# Carrier_for-Addons-V01-002.net
KiCad netlist of a schematic drawn in EAGLE
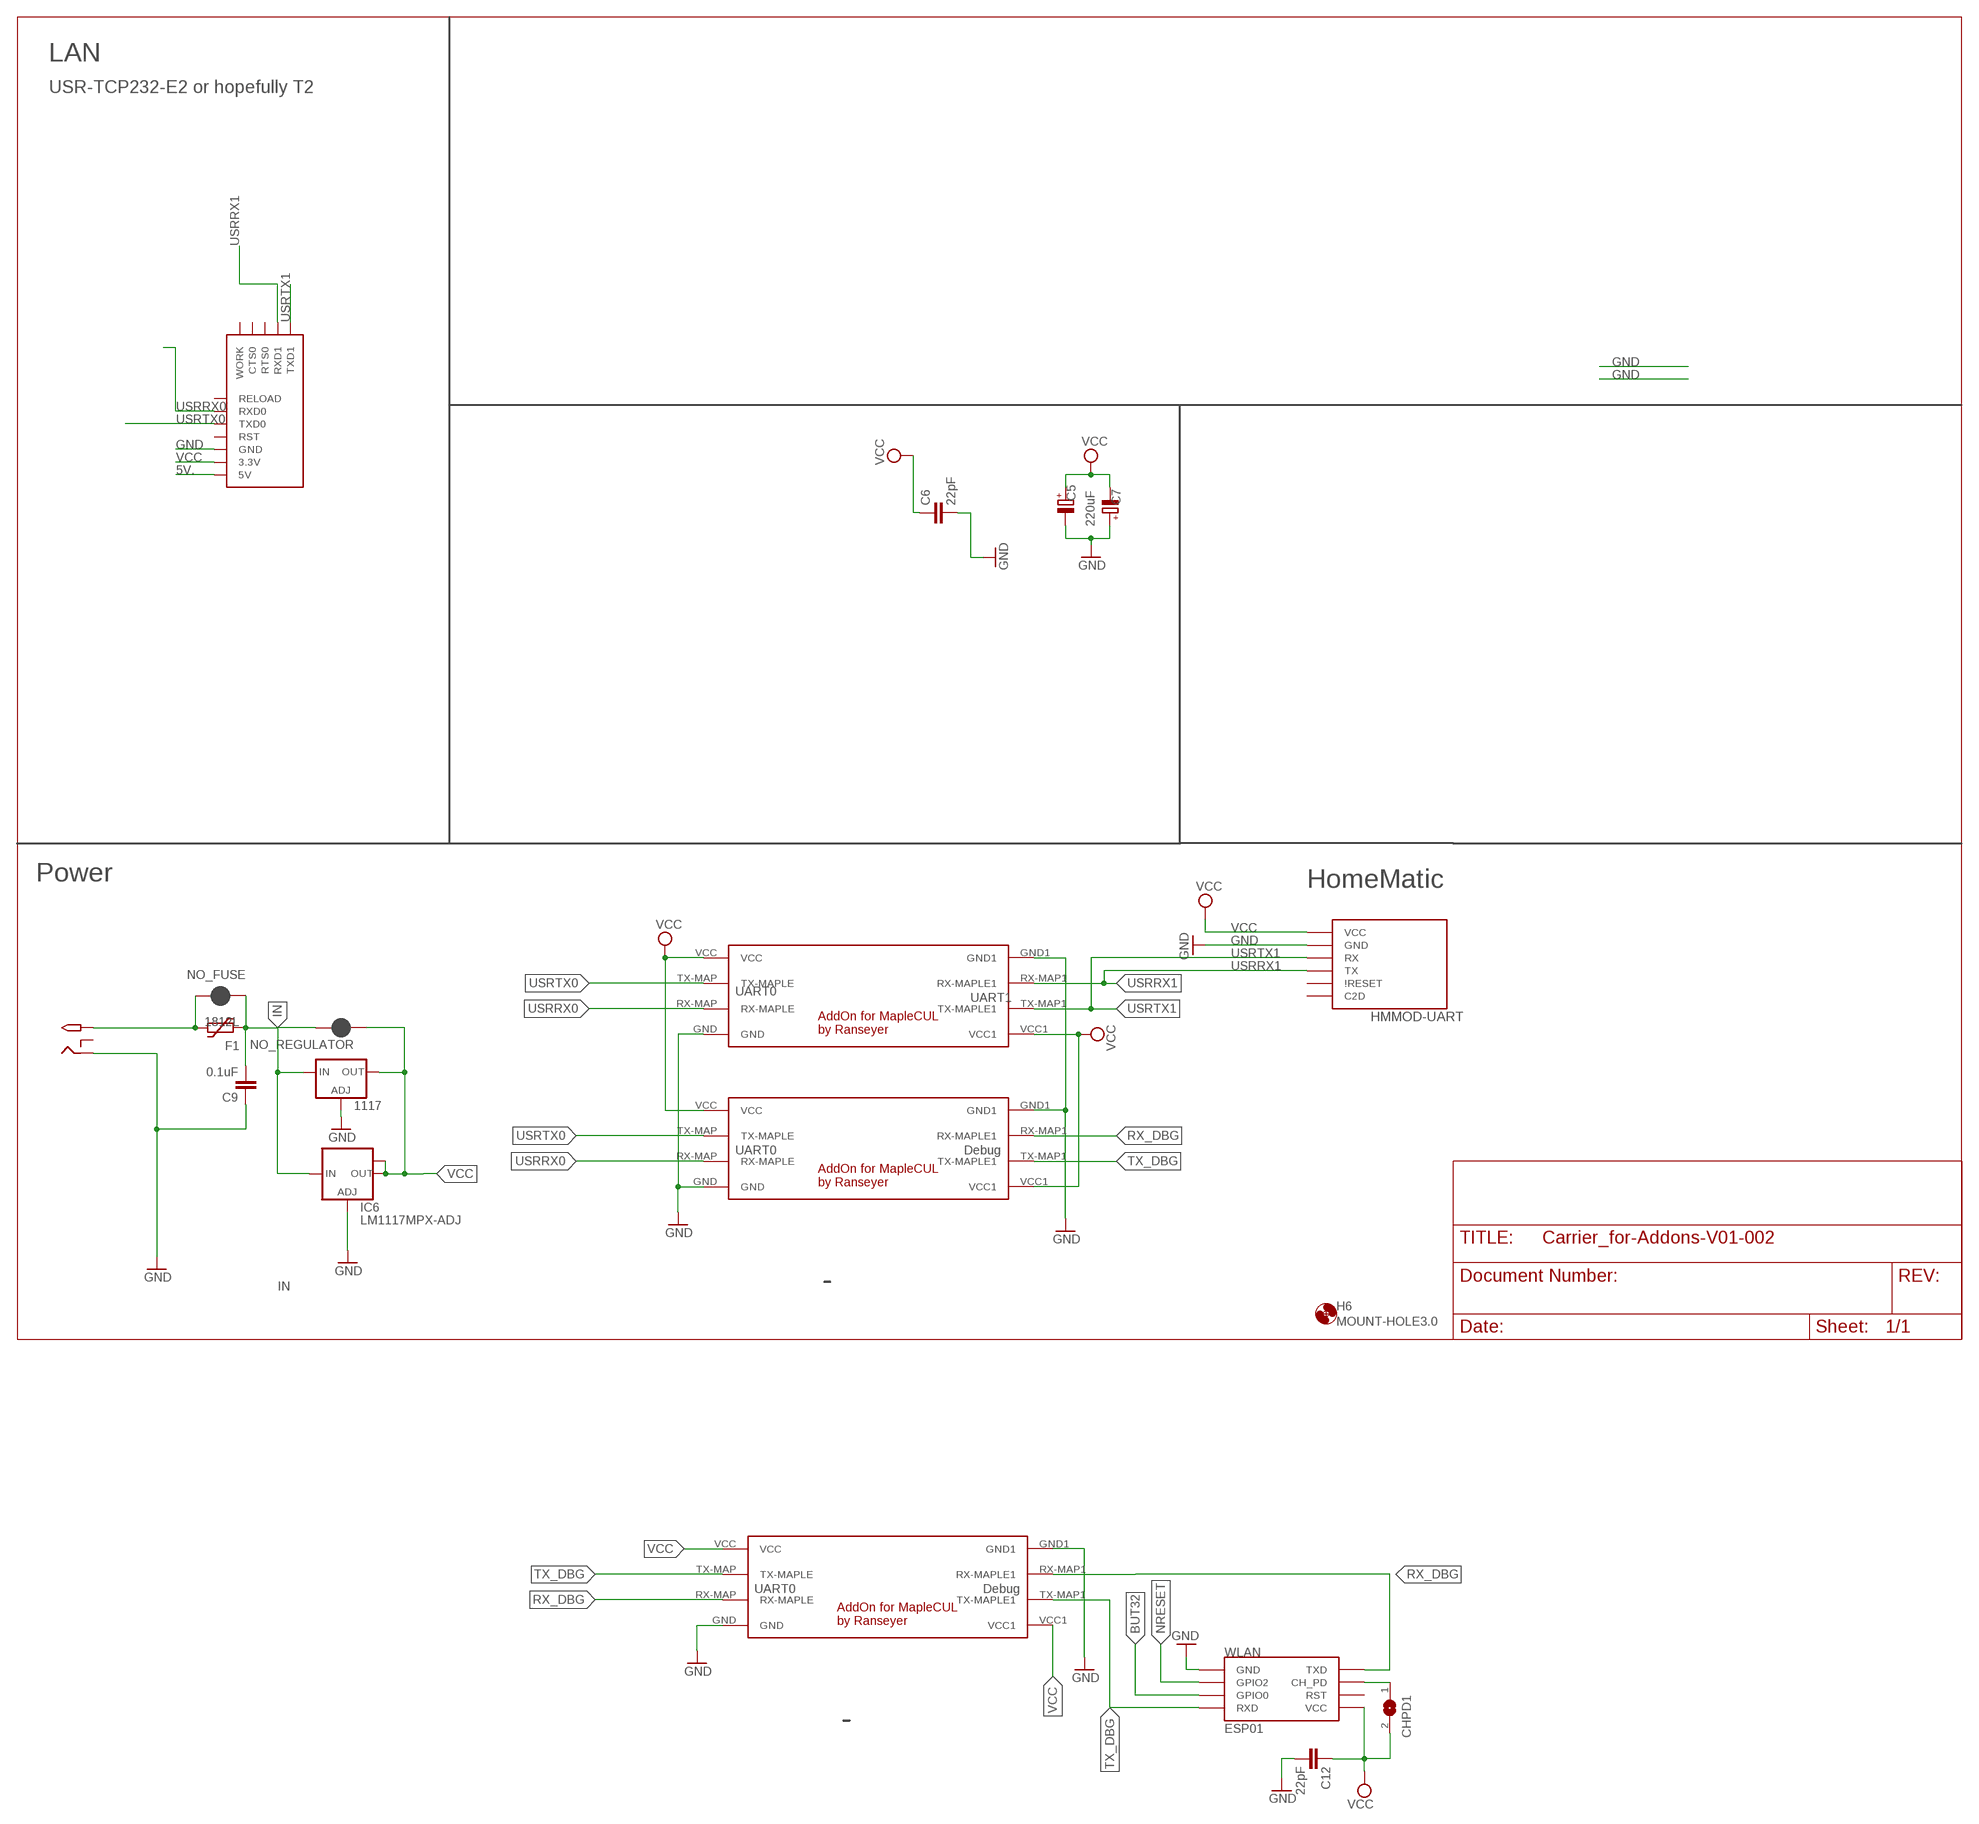
[diagram p0: schematic, sheet 1, part 1 of 2]
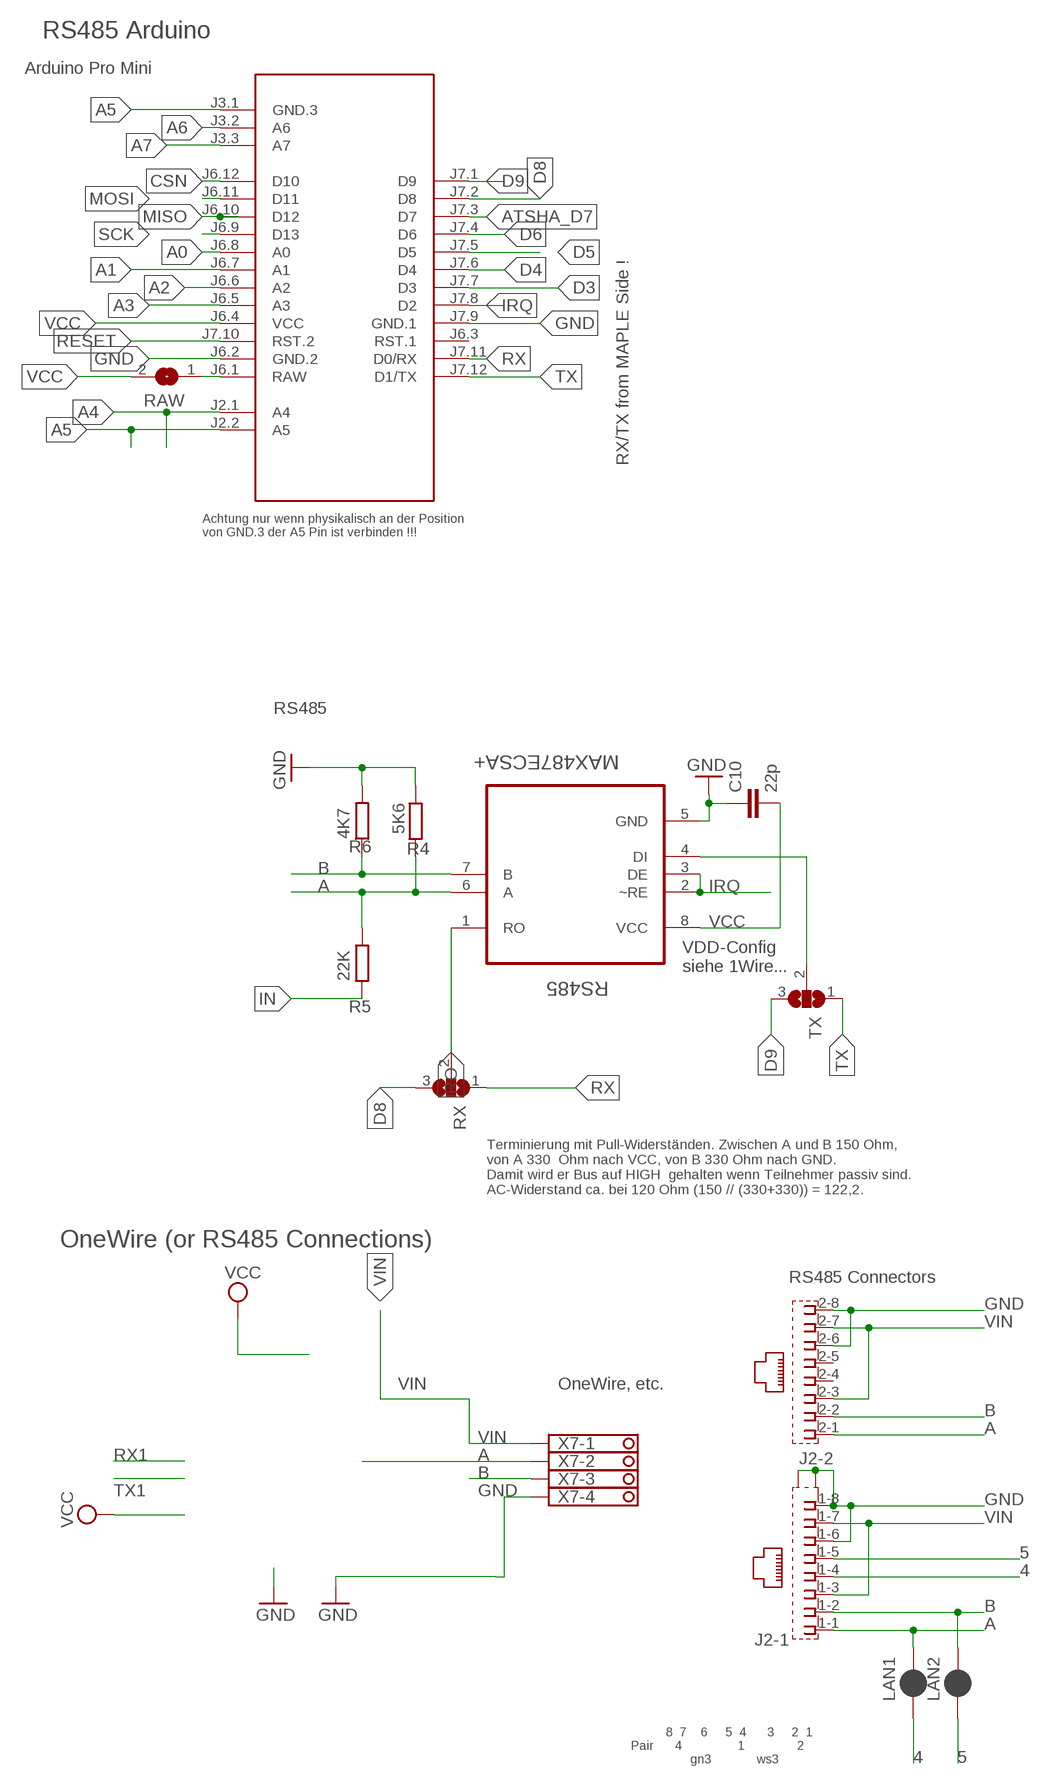
[diagram p1: schematic, sheet 1, part 2 of 2]

(export (version "E")
  (design (tool "Eeschema 10.0.6"))
  (components
    (comp (ref "1117")
      (value "LD117ADT50TR")
      (footprint "eagle-import:DPACK")
      (libsource (lib "eagle-import") (part "LD117A?DT50TR"))
    )
    (comp (ref "C5")
      (value "220uF")
      (footprint "eagle-import:E5-8,5")
      (libsource (lib "eagle-import") (part "CPOL-EUE5-8.5"))
    )
    (comp (ref "C6")
      (value "22pF")
      (footprint "eagle-import:C0805")
      (libsource (lib "eagle-import") (part "C-EUC0805"))
    )
    (comp (ref "C7")
      (value "CPOL-EUSMCE")
      (footprint "eagle-import:SMC_E")
      (libsource (lib "eagle-import") (part "rcl_334_CPOL-EUSMCE"))
    )
    (comp (ref "C9")
      (value "0.1uF")
      (footprint "eagle-import:C1206")
      (libsource (lib "eagle-import") (part "C-EUC1206"))
    )
    (comp (ref "C10")
      (value "22p")
      (footprint "eagle-import:C0805")
      (libsource (lib "eagle-import") (part "C-EUC0805"))
    )
    (comp (ref "C12")
      (value "22pF")
      (footprint "eagle-import:C0805")
      (libsource (lib "eagle-import") (part "C-EUC0805"))
    )
    (comp (ref "CHPD1")
      (value "SJ")
      (footprint "eagle-import:SJ")
      (libsource (lib "eagle-import") (part "jumper_252_SJ"))
    )
    (comp (ref "F1")
      (value "1812L")
      (footprint "eagle-import:1812L")
      (libsource (lib "eagle-import") (part "1812L"))
    )
    (comp (ref "H6")
      (value "MOUNT-HOLE3.0")
      (footprint "eagle-import:3,0")
      (libsource (lib "eagle-import") (part "MOUNT-HOLE3.0"))
    )
    (comp (ref "HMMOD-UART")
      (value "HM-MOD-UARTDIL")
      (footprint "eagle-import:HM-MOD-UART-DIL")
      (libsource (lib "eagle-import") (part "HM-MOD-UARTDIL"))
    )
    (comp (ref "IC6")
      (value "LM1117MPX-ADJ")
      (footprint "eagle-import:SOT223")
      (libsource (lib "eagle-import") (part "LM1117MPX-ADJ"))
    )
    (comp (ref "J2")
      (value "RJ45_2X_S")
      (footprint "eagle-import:RJ45_2X_S")
      (libsource (lib "eagle-import") (part "RJ45_2X_S"))
    )
    (comp (ref "LAN1")
      (value "JUMPER-SMT_2_NC_PASTE_SILK")
      (footprint "eagle-import:SMT-JUMPER_2_NC_PASTE_SILK")
      (libsource (lib "eagle-import") (part "JUMPER-SMT_2_NC_PASTE_SILK"))
    )
    (comp (ref "LAN2")
      (value "JUMPER-SMT_2_NC_PASTE_SILK")
      (footprint "eagle-import:SMT-JUMPER_2_NC_PASTE_SILK")
      (libsource (lib "eagle-import") (part "JUMPER-SMT_2_NC_PASTE_SILK"))
    )
    (comp (ref "M1")
      (value "ARDUINO-PRO-MINI-3.3V#NP")
      (footprint "eagle-import:ARDUINO-PRO-MINI#NP")
      (libsource (lib "eagle-import") (part "ARDUINO-PRO-MINI-#NP3.3V"))
    )
    (comp (ref "NO_FUSE")
      (value "JUMPER-SMT_2_NC_PASTE_NO-SILK")
      (footprint "eagle-import:SMT-JUMPER_2_NC_PASTE_NO-SILK")
      (libsource (lib "eagle-import") (part "SparkFun-Jumpers_528_JUMPER-SMT_2_NC_PASTE_NO-SILK"))
    )
    (comp (ref "NO_REGULATOR")
      (value "JUMPER-SMT_2_NC_PASTE_NO-SILK")
      (footprint "eagle-import:SMT-JUMPER_2_NC_PASTE_NO-SILK")
      (libsource (lib "eagle-import") (part "SparkFun-Jumpers_528_JUMPER-SMT_2_NC_PASTE_NO-SILK"))
    )
    (comp (ref "R4")
      (value "5K6")
      (footprint "eagle-import:R0805")
      (libsource (lib "eagle-import") (part "R-EU_R0805"))
    )
    (comp (ref "R5")
      (value "22K")
      (footprint "eagle-import:R0805")
      (libsource (lib "eagle-import") (part "R-EU_R0805"))
    )
    (comp (ref "R6")
      (value "4K7")
      (footprint "eagle-import:R0805")
      (libsource (lib "eagle-import") (part "R-EU_R0805"))
    )
    (comp (ref "RAW") (value "SJ") (footprint "eagle-import:SJ") (libsource (lib "eagle-import") (part "SJ")))
    (comp (ref "RS485")
      (value "MAX487ECSA+")
      (footprint "eagle-import:SOIC127P600X175-8N")
      (libsource (lib "eagle-import") (part "MAX487ECSA+"))
    )
    (comp (ref "RX")
      (value "SJ2W")
      (footprint "eagle-import:SJ_2")
      (libsource (lib "eagle-import") (part "SJ2W"))
    )
    (comp (ref "TX")
      (value "SJ2W")
      (footprint "eagle-import:SJ_2")
      (libsource (lib "eagle-import") (part "SJ2W"))
    )
    (comp (ref "U$1")
      (value "MAPLE-CUL-ADDON-V01")
      (footprint "eagle-import:MAPLE-CUL-V01")
      (libsource (lib "eagle-import") (part "MAPLE-CUL-ADDON-V01"))
    )
    (comp (ref "U$2")
      (value "2.1MMJACKTHM")
      (footprint "eagle-import:PJ-102A")
      (libsource (lib "eagle-import") (part "2.1MMJACKTHM"))
    )
    (comp (ref "U$3")
      (value "MAPLE-CUL-ADDON-V01")
      (footprint "eagle-import:MAPLE-CUL-V01")
      (libsource (lib "eagle-import") (part "MAPLE-CUL-ADDON-V01"))
    )
    (comp (ref "U$4")
      (value "MAPLE-CUL-ADDON-V01")
      (footprint "eagle-import:MAPLE-CUL-V01")
      (libsource (lib "eagle-import") (part "MAPLE-CUL-ADDON-V01"))
    )
    (comp (ref "U$5")
      (value "USR-TCP232-E2")
      (footprint "eagle-import:USR-TCP232-E2")
      (libsource (lib "eagle-import") (part "USR-TCP232-E2"))
    )
    (comp (ref "WLAN")
      (value "ESP01")
      (footprint "eagle-import:ESP01")
      (libsource (lib "eagle-import") (part "ESP01"))
    )
    (comp (ref "X7")
      (value "1751264")
      (footprint "eagle-import:1751264")
      (libsource (lib "eagle-import") (part "1751264"))
    )
  )
  (nets
    (net (code "1") (name "/4") (class "Default")
      (node (ref "J2") (pin "1-4") (pinfunction "4_1-4") (pintype "passive"))
      (node (ref "LAN1") (pin "1") (pinfunction "1_1") (pintype "passive"))
    )
    (net (code "2") (name "/5") (class "Default")
      (node (ref "J2") (pin "1-5") (pinfunction "5_1-5") (pintype "passive"))
      (node (ref "LAN2") (pin "1") (pinfunction "1_1") (pintype "passive"))
    )
    (net (code "3") (name "/5V.") (class "Default")
      (node (ref "U$5") (pin "5V") (pinfunction "5V_5V") (pintype "bidirectional"))
    )
    (net (code "4") (name "/A") (class "Default")
      (node (ref "J2") (pin "1-1") (pinfunction "1_1-1") (pintype "passive"))
      (node (ref "J2") (pin "2-1") (pinfunction "1_2-1") (pintype "passive"))
      (node (ref "LAN1") (pin "2") (pinfunction "2_2") (pintype "passive"))
      (node (ref "R4") (pin "2") (pinfunction "2_2") (pintype "passive"))
      (node (ref "R5") (pin "2") (pinfunction "2_2") (pintype "passive"))
      (node (ref "RS485") (pin "6") (pinfunction "A_6") (pintype "bidirectional"))
      (node (ref "X7") (pin "2") (pinfunction "K_2") (pintype "passive"))
    )
    (net (code "5") (name "/B") (class "Default")
      (node (ref "J2") (pin "1-2") (pinfunction "2_1-2") (pintype "passive"))
      (node (ref "J2") (pin "2-2") (pinfunction "2_2-2") (pintype "passive"))
      (node (ref "LAN2") (pin "2") (pinfunction "2_2") (pintype "passive"))
      (node (ref "R6") (pin "1") (pinfunction "1_1") (pintype "passive"))
      (node (ref "RS485") (pin "7") (pinfunction "B_7") (pintype "bidirectional"))
      (node (ref "X7") (pin "3") (pinfunction "K_3") (pintype "passive"))
    )
    (net (code "8") (name "A0") (class "Default")
      (node (ref "M1") (pin "J6.8") (pinfunction "A0_J6.8") (pintype "bidirectional"))
    )
    (net (code "9") (name "A1") (class "Default")
      (node (ref "M1") (pin "J6.7") (pinfunction "A1_J6.7") (pintype "bidirectional"))
    )
    (net (code "10") (name "A2") (class "Default")
      (node (ref "M1") (pin "J6.6") (pinfunction "A2_J6.6") (pintype "bidirectional"))
    )
    (net (code "11") (name "A3") (class "Default")
      (node (ref "M1") (pin "J6.5") (pinfunction "A3_J6.5") (pintype "bidirectional"))
    )
    (net (code "12") (name "A4") (class "Default")
      (node (ref "M1") (pin "J2.1") (pinfunction "A4_J2.1") (pintype "bidirectional"))
    )
    (net (code "13") (name "A5") (class "Default")
      (node (ref "M1") (pin "J2.2") (pinfunction "A5_J2.2") (pintype "bidirectional"))
      (node (ref "M1") (pin "J3.1") (pinfunction "GND.3_J3.1") (pintype "bidirectional"))
    )
    (net (code "14") (name "A6") (class "Default")
      (node (ref "M1") (pin "J3.2") (pinfunction "A6_J3.2") (pintype "bidirectional"))
    )
    (net (code "15") (name "A7") (class "Default")
      (node (ref "M1") (pin "J3.3") (pinfunction "A7_J3.3") (pintype "bidirectional"))
    )
    (net (code "16") (name "ATSHA_D7") (class "Default")
      (node (ref "M1") (pin "J7.3") (pinfunction "D7_J7.3") (pintype "bidirectional"))
    )
    (net (code "17") (name "BUT32") (class "Default")
      (node (ref "WLAN") (pin "GPIO0") (pinfunction "GPIO0_GPIO0") (pintype "bidirectional"))
    )
    (net (code "18") (name "CSN") (class "Default")
      (node (ref "M1") (pin "J6.12") (pinfunction "D10_J6.12") (pintype "bidirectional"))
    )
    (net (code "19") (name "D3") (class "Default")
      (node (ref "M1") (pin "J7.7") (pinfunction "D3_J7.7") (pintype "bidirectional"))
    )
    (net (code "20") (name "D4") (class "Default")
      (node (ref "M1") (pin "J7.6") (pinfunction "D4_J7.6") (pintype "bidirectional"))
    )
    (net (code "21") (name "D5") (class "Default")
      (node (ref "M1") (pin "J7.5") (pinfunction "D5_J7.5") (pintype "bidirectional"))
    )
    (net (code "22") (name "D6") (class "Default")
      (node (ref "M1") (pin "J7.4") (pinfunction "D6_J7.4") (pintype "bidirectional"))
    )
    (net (code "23") (name "D8") (class "Default")
      (node (ref "M1") (pin "J7.2") (pinfunction "D8_J7.2") (pintype "bidirectional"))
      (node (ref "RX") (pin "3") (pinfunction "3_3") (pintype "passive"))
    )
    (net (code "24") (name "D9") (class "Default")
      (node (ref "M1") (pin "J7.1") (pinfunction "D9_J7.1") (pintype "bidirectional"))
      (node (ref "TX") (pin "3") (pinfunction "3_3") (pintype "passive"))
    )
    (net (code "25") (name "GND") (class "Default")
      (node (ref "1117") (pin "1") (pinfunction "ADJ_1") (pintype "input"))
      (node (ref "C10") (pin "1") (pinfunction "1_1") (pintype "passive"))
      (node (ref "C12") (pin "2") (pinfunction "2_2") (pintype "passive"))
      (node (ref "C5") (pin "-") (pinfunction "-_-") (pintype "passive"))
      (node (ref "C6") (pin "2") (pinfunction "2_2") (pintype "passive"))
      (node (ref "C7") (pin "+") (pinfunction "+_+") (pintype "passive"))
      (node (ref "C9") (pin "1") (pinfunction "1_1") (pintype "passive"))
      (node (ref "HMMOD-UART") (pin "2") (pinfunction "GND_2") (pintype "power_in"))
      (node (ref "IC6") (pin "1") (pinfunction "ADJ_1") (pintype "input"))
      (node (ref "J2") (pin "1-6") (pinfunction "6_1-6") (pintype "passive"))
      (node (ref "J2") (pin "1-8") (pinfunction "8_1-8") (pintype "passive"))
      (node (ref "J2") (pin "2-6") (pinfunction "6_2-6") (pintype "passive"))
      (node (ref "J2") (pin "2-8") (pinfunction "8_2-8") (pintype "passive"))
      (node (ref "J2") (pin "G1") (pinfunction "S2_G1") (pintype "passive"))
      (node (ref "J2") (pin "G3") (pinfunction "S1_G3") (pintype "passive"))
      (node (ref "M1") (pin "J6.2") (pinfunction "GND.2_J6.2") (pintype "power_in"))
      (node (ref "M1") (pin "J7.9") (pinfunction "GND.1_J7.9") (pintype "power_in"))
      (node (ref "R4") (pin "1") (pinfunction "1_1") (pintype "passive"))
      (node (ref "R6") (pin "2") (pinfunction "2_2") (pintype "passive"))
      (node (ref "RS485") (pin "5") (pinfunction "GND_5") (pintype "passive"))
      (node (ref "U$1") (pin "GND") (pinfunction "GND_GND") (pintype "bidirectional"))
      (node (ref "U$1") (pin "GND1") (pinfunction "GND1_GND1") (pintype "bidirectional"))
      (node (ref "U$2") (pin "RING") (pinfunction "RING_RING") (pintype "bidirectional"))
      (node (ref "U$3") (pin "GND") (pinfunction "GND_GND") (pintype "bidirectional"))
      (node (ref "U$3") (pin "GND1") (pinfunction "GND1_GND1") (pintype "bidirectional"))
      (node (ref "U$4") (pin "GND") (pinfunction "GND_GND") (pintype "bidirectional"))
      (node (ref "U$4") (pin "GND1") (pinfunction "GND1_GND1") (pintype "bidirectional"))
      (node (ref "U$5") (pin "GND") (pinfunction "GND_GND") (pintype "bidirectional"))
      (node (ref "WLAN") (pin "GND") (pinfunction "GND_GND") (pintype "bidirectional"))
      (node (ref "X7") (pin "4") (pinfunction "K_4") (pintype "passive"))
    )
    (net (code "26") (name "IN") (class "Default")
      (node (ref "1117") (pin "3") (pinfunction "IN_3") (pintype "input"))
      (node (ref "C9") (pin "2") (pinfunction "2_2") (pintype "passive"))
      (node (ref "F1") (pin "P$1") (pinfunction "1_P$1") (pintype "passive"))
      (node (ref "IC6") (pin "3") (pinfunction "IN_3") (pintype "input"))
      (node (ref "NO_FUSE") (pin "1") (pinfunction "1_1") (pintype "passive"))
      (node (ref "NO_REGULATOR") (pin "2") (pinfunction "2_2") (pintype "passive"))
      (node (ref "R5") (pin "1") (pinfunction "1_1") (pintype "passive"))
    )
    (net (code "27") (name "IRQ") (class "Default")
      (node (ref "M1") (pin "J7.8") (pinfunction "D2_J7.8") (pintype "bidirectional"))
      (node (ref "RS485") (pin "2") (pinfunction "~{RE}_2") (pintype "input"))
      (node (ref "RS485") (pin "3") (pinfunction "DE_3") (pintype "input"))
    )
    (net (code "28") (name "MISO") (class "Default")
      (node (ref "M1") (pin "J6.10") (pinfunction "D12_J6.10") (pintype "bidirectional"))
    )
    (net (code "29") (name "MOSI") (class "Default")
      (node (ref "M1") (pin "J6.11") (pinfunction "D11_J6.11") (pintype "bidirectional"))
    )
    (net (code "30") (name "NRESET") (class "Default")
      (node (ref "WLAN") (pin "GPIO2") (pinfunction "GPIO2_GPIO2") (pintype "bidirectional"))
    )
    (net (code "31") (name "Net-(CHPD1-Pad1)") (class "Default")
      (node (ref "CHPD1") (pin "1") (pinfunction "1_1") (pintype "passive"))
      (node (ref "WLAN") (pin "CH_PD") (pinfunction "CH_PD_CH_PD") (pintype "bidirectional"))
    )
    (net (code "32") (name "Net-(M1-RAW)") (class "Default")
      (node (ref "M1") (pin "J6.1") (pinfunction "RAW_J6.1") (pintype "power_in"))
      (node (ref "RAW") (pin "1") (pinfunction "1_1") (pintype "passive"))
    )
    (net (code "33") (name "Net-(RS485-DI)") (class "Default")
      (node (ref "RS485") (pin "4") (pinfunction "DI_4") (pintype "input"))
      (node (ref "TX") (pin "2") (pinfunction "2_2") (pintype "passive"))
    )
    (net (code "34") (name "RESET") (class "Default")
      (node (ref "M1") (pin "J7.10") (pinfunction "RST.2_J7.10") (pintype "bidirectional"))
    )
    (net (code "35") (name "RO") (class "Default")
      (node (ref "RS485") (pin "1") (pinfunction "RO_1") (pintype "output"))
      (node (ref "RX") (pin "2") (pinfunction "2_2") (pintype "passive"))
    )
    (net (code "36") (name "RX") (class "Default")
      (node (ref "M1") (pin "J7.11") (pinfunction "D0/RX_J7.11") (pintype "bidirectional"))
      (node (ref "RX") (pin "1") (pinfunction "1_1") (pintype "passive"))
    )
    (net (code "37") (name "RX_DBG") (class "Default")
      (node (ref "U$1") (pin "RX-MAP") (pinfunction "RX-MAPLE_RX-MAP") (pintype "bidirectional"))
      (node (ref "U$1") (pin "RX-MAP1") (pinfunction "RX-MAPLE1_RX-MAP1") (pintype "bidirectional"))
      (node (ref "U$4") (pin "RX-MAP1") (pinfunction "RX-MAPLE1_RX-MAP1") (pintype "bidirectional"))
      (node (ref "WLAN") (pin "TX") (pinfunction "TXD_TX") (pintype "bidirectional"))
    )
    (net (code "38") (name "SCK") (class "Default")
      (node (ref "M1") (pin "J6.9") (pinfunction "D13_J6.9") (pintype "bidirectional"))
    )
    (net (code "39") (name "TX") (class "Default")
      (node (ref "M1") (pin "J7.12") (pinfunction "D1/TX_J7.12") (pintype "bidirectional"))
      (node (ref "TX") (pin "1") (pinfunction "1_1") (pintype "passive"))
    )
    (net (code "40") (name "TX_DBG") (class "Default")
      (node (ref "U$1") (pin "TX-MAP") (pinfunction "TX-MAPLE_TX-MAP") (pintype "bidirectional"))
      (node (ref "U$1") (pin "TX-MAP1") (pinfunction "TX-MAPLE1_TX-MAP1") (pintype "bidirectional"))
      (node (ref "U$4") (pin "TX-MAP1") (pinfunction "TX-MAPLE1_TX-MAP1") (pintype "bidirectional"))
      (node (ref "WLAN") (pin "RX") (pinfunction "RXD_RX") (pintype "bidirectional"))
    )
    (net (code "41") (name "USRRX0") (class "Default")
      (node (ref "U$3") (pin "RX-MAP") (pinfunction "RX-MAPLE_RX-MAP") (pintype "bidirectional"))
      (node (ref "U$4") (pin "RX-MAP") (pinfunction "RX-MAPLE_RX-MAP") (pintype "bidirectional"))
      (node (ref "U$5") (pin "RXD0") (pinfunction "RXD0_RXD0") (pintype "input"))
    )
    (net (code "42") (name "USRRX1") (class "Default")
      (node (ref "HMMOD-UART") (pin "5") (pinfunction "TX_5") (pintype "bidirectional"))
      (node (ref "U$3") (pin "RX-MAP1") (pinfunction "RX-MAPLE1_RX-MAP1") (pintype "bidirectional"))
      (node (ref "U$5") (pin "RXD1") (pinfunction "RXD1_RXD1") (pintype "input"))
    )
    (net (code "43") (name "USRTX0") (class "Default")
      (node (ref "U$3") (pin "TX-MAP") (pinfunction "TX-MAPLE_TX-MAP") (pintype "bidirectional"))
      (node (ref "U$4") (pin "TX-MAP") (pinfunction "TX-MAPLE_TX-MAP") (pintype "bidirectional"))
      (node (ref "U$5") (pin "TXD0") (pinfunction "TXD0_TXD0") (pintype "output"))
    )
    (net (code "44") (name "USRTX1") (class "Default")
      (node (ref "HMMOD-UART") (pin "6") (pinfunction "RX_6") (pintype "bidirectional"))
      (node (ref "U$3") (pin "TX-MAP1") (pinfunction "TX-MAPLE1_TX-MAP1") (pintype "bidirectional"))
      (node (ref "U$5") (pin "TXD1") (pinfunction "TXD1_TXD1") (pintype "output"))
    )
    (net (code "45") (name "VCC") (class "Default")
      (node (ref "1117") (pin "4") (pinfunction "OUT_4") (pintype "passive"))
      (node (ref "C10") (pin "2") (pinfunction "2_2") (pintype "passive"))
      (node (ref "C12") (pin "1") (pinfunction "1_1") (pintype "passive"))
      (node (ref "C5") (pin "+") (pinfunction "+_+") (pintype "passive"))
      (node (ref "C6") (pin "1") (pinfunction "1_1") (pintype "passive"))
      (node (ref "C7") (pin "-") (pinfunction "-_-") (pintype "passive"))
      (node (ref "CHPD1") (pin "2") (pinfunction "2_2") (pintype "passive"))
      (node (ref "HMMOD-UART") (pin "1") (pinfunction "VCC_1") (pintype "power_in"))
      (node (ref "IC6") (pin "2") (pinfunction "OUT_2") (pintype "passive"))
      (node (ref "IC6") (pin "TAB") (pinfunction "OUT1_TAB") (pintype "passive"))
      (node (ref "M1") (pin "J6.4") (pinfunction "VCC_J6.4") (pintype "power_in"))
      (node (ref "NO_REGULATOR") (pin "1") (pinfunction "1_1") (pintype "passive"))
      (node (ref "RAW") (pin "2") (pinfunction "2_2") (pintype "passive"))
      (node (ref "RS485") (pin "8") (pinfunction "VCC_8") (pintype "power_in"))
      (node (ref "U$1") (pin "VCC") (pinfunction "VCC_VCC") (pintype "bidirectional"))
      (node (ref "U$1") (pin "VCC1") (pinfunction "VCC1_VCC1") (pintype "bidirectional"))
      (node (ref "U$3") (pin "VCC") (pinfunction "VCC_VCC") (pintype "bidirectional"))
      (node (ref "U$3") (pin "VCC1") (pinfunction "VCC1_VCC1") (pintype "bidirectional"))
      (node (ref "U$4") (pin "VCC") (pinfunction "VCC_VCC") (pintype "bidirectional"))
      (node (ref "U$4") (pin "VCC1") (pinfunction "VCC1_VCC1") (pintype "bidirectional"))
      (node (ref "U$5") (pin "3.3V") (pinfunction "3.3V_3.3V") (pintype "bidirectional"))
      (node (ref "WLAN") (pin "VCC") (pinfunction "VCC_VCC") (pintype "bidirectional"))
    )
    (net (code "46") (name "VIN") (class "Default")
      (node (ref "F1") (pin "P$2") (pinfunction "2_P$2") (pintype "passive"))
      (node (ref "J2") (pin "1-3") (pinfunction "3_1-3") (pintype "passive"))
      (node (ref "J2") (pin "1-7") (pinfunction "7_1-7") (pintype "passive"))
      (node (ref "J2") (pin "2-3") (pinfunction "3_2-3") (pintype "passive"))
      (node (ref "J2") (pin "2-7") (pinfunction "7_2-7") (pintype "passive"))
      (node (ref "NO_FUSE") (pin "2") (pinfunction "2_2") (pintype "passive"))
      (node (ref "U$2") (pin "TIP") (pinfunction "TIP_TIP") (pintype "bidirectional"))
      (node (ref "X7") (pin "1") (pinfunction "K_1") (pintype "passive"))
    )
    (net (code "47") (name "unconnected-(HMMOD-UART-C2D-Pad3)") (class "Default")
      (node (ref "HMMOD-UART") (pin "3") (pinfunction "C2D_3") (pintype "bidirectional"))
    )
    (net (code "48") (name "unconnected-(HMMOD-UART-\\~{RESET}-Pad4)") (class "Default")
      (node (ref "HMMOD-UART") (pin "4") (pinfunction "\\~{RESET}_4") (pintype "bidirectional"))
    )
    (net (code "49") (name "unconnected-(J2B-4-Pad2-4)") (class "Default")
      (node (ref "J2") (pin "2-4") (pinfunction "4_2-4") (pintype "passive"))
    )
    (net (code "50") (name "unconnected-(J2B-5-Pad2-5)") (class "Default")
      (node (ref "J2") (pin "2-5") (pinfunction "5_2-5") (pintype "passive"))
    )
    (net (code "51") (name "unconnected-(M1-RST.1-PadJ6.3)") (class "Default")
      (node (ref "M1") (pin "J6.3") (pinfunction "RST.1_J6.3") (pintype "bidirectional"))
    )
    (net (code "52") (name "unconnected-(U$2-PadRING_SW)") (class "Default")
      (node (ref "U$2") (pin "RING_SW") (pinfunction "RING_SW_RING_SW") (pintype "bidirectional"))
    )
    (net (code "53") (name "unconnected-(U$5-PadCTS0)") (class "Default")
      (node (ref "U$5") (pin "CTS0") (pinfunction "CTS0_CTS0") (pintype "bidirectional"))
    )
    (net (code "54") (name "unconnected-(U$5-PadRELOAD)") (class "Default")
      (node (ref "U$5") (pin "RELOAD") (pinfunction "RELOAD_RELOAD") (pintype "bidirectional"))
    )
    (net (code "55") (name "unconnected-(U$5-PadRST)") (class "Default")
      (node (ref "U$5") (pin "RST") (pinfunction "RST_RST") (pintype "bidirectional"))
    )
    (net (code "56") (name "unconnected-(U$5-PadRTS0)") (class "Default")
      (node (ref "U$5") (pin "RTS0") (pinfunction "RTS0_RTS0") (pintype "bidirectional"))
    )
    (net (code "57") (name "unconnected-(U$5-PadWORK)") (class "Default")
      (node (ref "U$5") (pin "WORK") (pinfunction "WORK_WORK") (pintype "bidirectional"))
    )
    (net (code "58") (name "unconnected-(WLAN-PadRST)") (class "Default")
      (node (ref "WLAN") (pin "RST") (pinfunction "RST_RST") (pintype "bidirectional"))
    )
  )
)
